# alps-skc-1.net
KiCad netlist of a schematic drawn in EAGLE
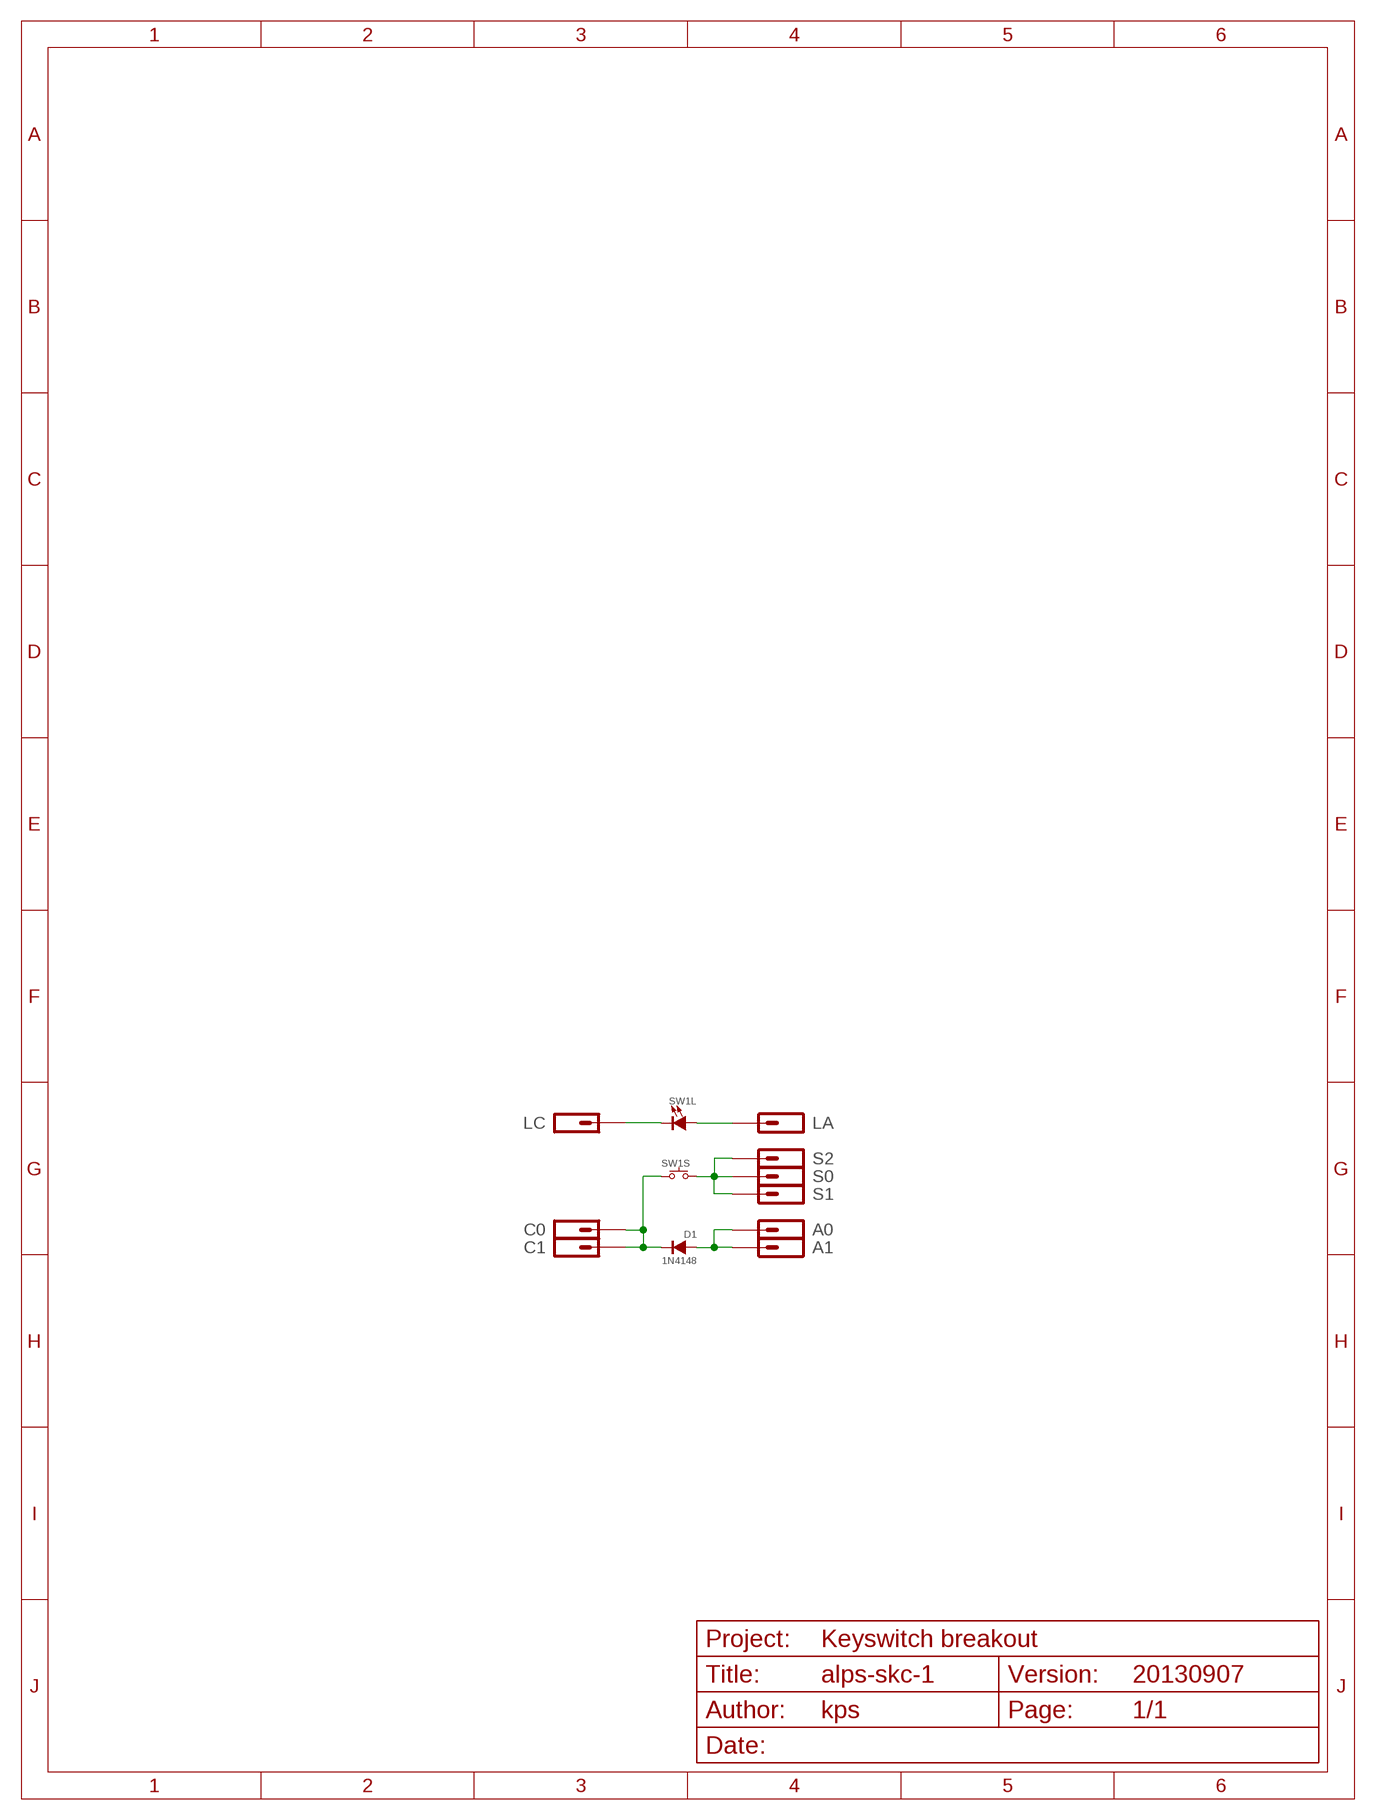
[diagram p0: schematic, sheet 1]

(export (version "E")
  (design (tool "Eeschema 10.0.6"))
  (components
    (comp (ref "A0")
      (value "J-1-SQUARE-70")
      (footprint "eagle-import:J-1-SQUARE-70")
      (libsource (lib "eagle-import") (part "J-1-SQUARE-70"))
    )
    (comp (ref "A1")
      (value "J-1-SQUARE-74")
      (footprint "eagle-import:J-1-SQUARE-74")
      (libsource (lib "eagle-import") (part "J-1-SQUARE-74"))
    )
    (comp (ref "C0")
      (value "J-1-SQUARE-70")
      (footprint "eagle-import:J-1-SQUARE-70")
      (libsource (lib "eagle-import") (part "J-1-SQUARE-70"))
    )
    (comp (ref "C1")
      (value "J-1-SQUARE-74")
      (footprint "eagle-import:J-1-SQUARE-74")
      (libsource (lib "eagle-import") (part "J-1-SQUARE-74"))
    )
    (comp (ref "D1")
      (value "1N4148")
      (footprint "eagle-import:SMA+SOD323-P-NOSS")
      (libsource (lib "eagle-import") (part "DIODE-SMA+SOD323-NOSS"))
    )
    (comp (ref "LA")
      (value "J-1-OCTAGON-70")
      (footprint "eagle-import:J-1-OCTAGON-70")
      (libsource (lib "eagle-import") (part "J-1-OCTAGON-70"))
    )
    (comp (ref "LC")
      (value "J-1-OCTAGON-70")
      (footprint "eagle-import:J-1-OCTAGON-70")
      (libsource (lib "eagle-import") (part "J-1-OCTAGON-70"))
    )
    (comp (ref "S0")
      (value "J-1-ROUND-70")
      (footprint "eagle-import:J-1-ROUND-70")
      (libsource (lib "eagle-import") (part "J-1-ROUND-70"))
    )
    (comp (ref "S1")
      (value "J-1-ROUND-74")
      (footprint "eagle-import:J-1-ROUND-74")
      (libsource (lib "eagle-import") (part "J-1-ROUND-74"))
    )
    (comp (ref "S2")
      (value "J-1-ROUND-74")
      (footprint "eagle-import:J-1-ROUND-74")
      (libsource (lib "eagle-import") (part "J-1-ROUND-74"))
    )
    (comp (ref "SW1")
      (value "SW-ALPS-SKC-LED")
      (footprint "eagle-import:SW-ALPS-SKC-LED")
      (libsource (lib "eagle-import") (part "SW-ALPS-SKC-LED"))
    )
  )
  (nets
    (net (code "1") (name "Net-(A0-Pad1)") (class "Default")
      (node (ref "A0") (pin "1") (pinfunction "1_1") (pintype "passive"))
      (node (ref "A1") (pin "1") (pinfunction "1_1") (pintype "passive"))
      (node (ref "D1") (pin "A") (pinfunction "A_A") (pintype "passive"))
    )
    (net (code "2") (name "Net-(SW1A-A)") (class "Default")
      (node (ref "LA") (pin "1") (pinfunction "1_1") (pintype "passive"))
      (node (ref "SW1") (pin "LA") (pinfunction "A_LA") (pintype "passive"))
    )
    (net (code "3") (name "Net-(SW1A-C)") (class "Default")
      (node (ref "LC") (pin "1") (pinfunction "1_1") (pintype "passive"))
      (node (ref "SW1") (pin "LC") (pinfunction "C_LC") (pintype "passive"))
    )
    (net (code "4") (name "Net-(SW1B-1)") (class "Default")
      (node (ref "C0") (pin "1") (pinfunction "1_1") (pintype "passive"))
      (node (ref "C1") (pin "1") (pinfunction "1_1") (pintype "passive"))
      (node (ref "D1") (pin "C") (pinfunction "C_C") (pintype "passive"))
      (node (ref "SW1") (pin "S1") (pinfunction "1_S1") (pintype "passive"))
    )
    (net (code "5") (name "Net-(SW1B-2)") (class "Default")
      (node (ref "S0") (pin "1") (pinfunction "1_1") (pintype "passive"))
      (node (ref "S1") (pin "1") (pinfunction "1_1") (pintype "passive"))
      (node (ref "S2") (pin "1") (pinfunction "1_1") (pintype "passive"))
      (node (ref "SW1") (pin "S2") (pinfunction "2_S2") (pintype "passive"))
    )
  )
)
